# Robot_arm.net
KiCad netlist of a schematic drawn in EAGLE
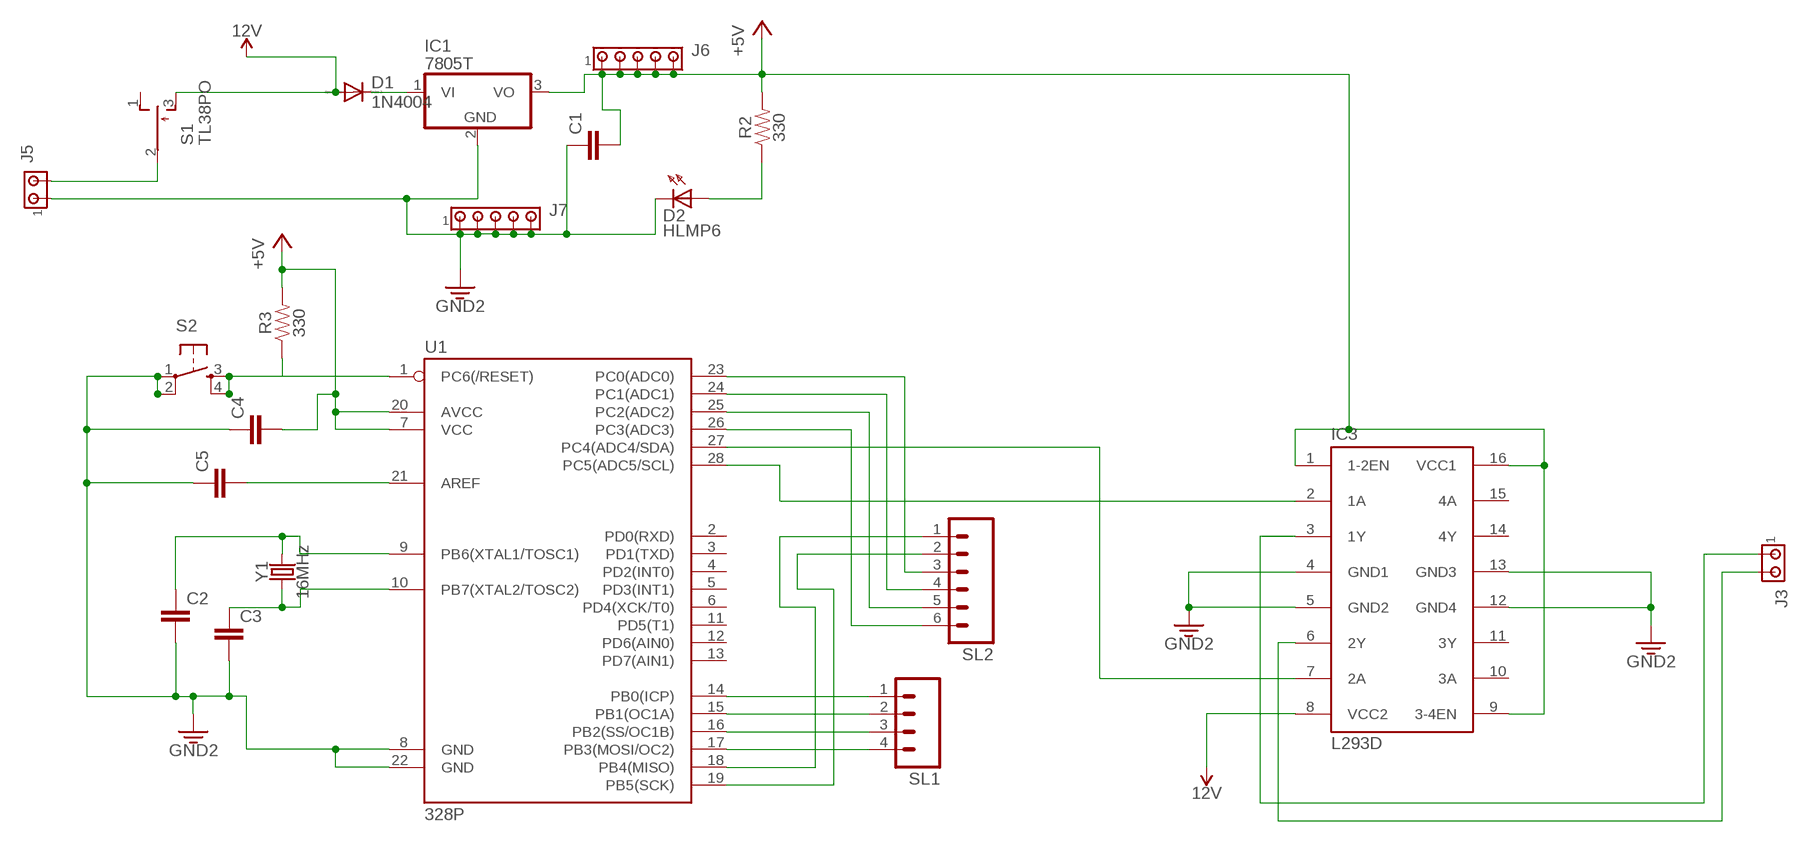
[diagram p0: schematic, sheet 1]

(export (version "E")
  (design (tool "Eeschema 10.0.6"))
  (components
    (comp (ref "C1")
      (value "C5/2.5")
      (footprint "eagle-import:C5B2.5")
      (libsource (lib "eagle-import") (part "C5/2.5"))
    )
    (comp (ref "C2")
      (value "C5/2.5")
      (footprint "eagle-import:C5B2.5")
      (libsource (lib "eagle-import") (part "C5/2.5"))
    )
    (comp (ref "C3")
      (value "C5/2.5")
      (footprint "eagle-import:C5B2.5")
      (libsource (lib "eagle-import") (part "C5/2.5"))
    )
    (comp (ref "C4")
      (value "C5/2.5")
      (footprint "eagle-import:C5B2.5")
      (libsource (lib "eagle-import") (part "C5/2.5"))
    )
    (comp (ref "C5")
      (value "C5/2.5")
      (footprint "eagle-import:C5B2.5")
      (libsource (lib "eagle-import") (part "C5/2.5"))
    )
    (comp (ref "D1")
      (value "1N4004")
      (footprint "eagle-import:DO41-10")
      (libsource (lib "eagle-import") (part "1N4004"))
    )
    (comp (ref "D2")
      (value "HLMP6")
      (footprint "eagle-import:HLMP6")
      (fields (field (name "MF") "AGILENT TECHNOLOGIES") (field (name "MPN") "HLMP-6500"))
      (libsource (lib "eagle-import") (part "HLMP6"))
    )
    (comp (ref "IC1")
      (value "7805T")
      (footprint "eagle-import:TO220H")
      (libsource (lib "eagle-import") (part "78T05"))
    )
    (comp (ref "IC3")
      (value "L293D")
      (footprint "eagle-import:DIL16")
      (libsource (lib "eagle-import") (part "L293D"))
    )
    (comp (ref "J3")
      (value "MTA02-156")
      (footprint "eagle-import:1X2MTA")
      (libsource (lib "eagle-import") (part "MTA02-156"))
    )
    (comp (ref "J5")
      (value "MTA02-156")
      (footprint "eagle-import:1X2MTA")
      (libsource (lib "eagle-import") (part "MTA02-156"))
    )
    (comp (ref "J6")
      (value "MTA05-100")
      (footprint "eagle-import:10X05MTA")
      (libsource (lib "eagle-import") (part "MTA05-100"))
    )
    (comp (ref "J7")
      (value "MTA05-100")
      (footprint "eagle-import:10X05MTA")
      (libsource (lib "eagle-import") (part "MTA05-100"))
    )
    (comp (ref "R2")
      (value "330")
      (footprint "eagle-import:AXIAL-0.3")
      (libsource (lib "eagle-import") (part "330OHM-HORIZ-1/10W-5%"))
    )
    (comp (ref "R3")
      (value "330")
      (footprint "eagle-import:AXIAL-0.3")
      (libsource (lib "eagle-import") (part "330OHM-HORIZ-1/10W-5%"))
    )
    (comp (ref "S1")
      (value "TL38PO")
      (footprint "eagle-import:TL3XPO")
      (libsource (lib "eagle-import") (part "TL38PO"))
    )
    (comp (ref "S2")
      (value "TAC_SWITCHPTH")
      (footprint "eagle-import:TACTILE-PTH")
      (libsource (lib "eagle-import") (part "TAC_SWITCHPTH"))
    )
    (comp (ref "SL1")
      (value "MA04")
      (footprint "eagle-import:04PA")
      (libsource (lib "eagle-import") (part "MA04"))
    )
    (comp (ref "SL2")
      (value "MA06")
      (footprint "eagle-import:06PA")
      (libsource (lib "eagle-import") (part "MA06"))
    )
    (comp (ref "U1")
      (value "328P")
      (footprint "eagle-import:DIP28")
      (libsource (lib "eagle-import") (part "ATMEGA328P_PDIP"))
    )
    (comp (ref "Y1")
      (value "16MHz")
      (footprint "eagle-import:HC49US")
      (libsource (lib "eagle-import") (part "CRYSTAL-16MHZPTH-HC49US"))
    )
  )
  (nets
    (net (code "1") (name "+5V") (class "Default")
      (node (ref "C1") (pin "2") (pinfunction "2_2") (pintype "passive"))
      (node (ref "C4") (pin "2") (pinfunction "2_2") (pintype "passive"))
      (node (ref "IC1") (pin "3") (pinfunction "VO_3") (pintype "passive"))
      (node (ref "IC3") (pin "1") (pinfunction "1-2EN_1") (pintype "input"))
      (node (ref "IC3") (pin "16") (pinfunction "VCC1_16") (pintype "power_in"))
      (node (ref "IC3") (pin "9") (pinfunction "3-4EN_9") (pintype "input"))
      (node (ref "J6") (pin "1") (pinfunction "1_1") (pintype "passive"))
      (node (ref "J6") (pin "2") (pinfunction "2_2") (pintype "passive"))
      (node (ref "J6") (pin "3") (pinfunction "3_3") (pintype "passive"))
      (node (ref "J6") (pin "4") (pinfunction "4_4") (pintype "passive"))
      (node (ref "J6") (pin "5") (pinfunction "5_5") (pintype "passive"))
      (node (ref "R2") (pin "P$2") (pinfunction "2_P$2") (pintype "passive"))
      (node (ref "R3") (pin "P$2") (pinfunction "2_P$2") (pintype "passive"))
      (node (ref "U1") (pin "20") (pinfunction "AVCC_20") (pintype "bidirectional"))
      (node (ref "U1") (pin "7") (pinfunction "VCC_7") (pintype "bidirectional"))
    )
    (net (code "2") (name "12V") (class "Default")
      (node (ref "D1") (pin "A") (pinfunction "A_A") (pintype "passive"))
      (node (ref "IC3") (pin "8") (pinfunction "VCC2_8") (pintype "power_in"))
      (node (ref "S1") (pin "3") (pinfunction "S_3") (pintype "passive"))
    )
    (net (code "3") (name "GND2") (class "Default")
      (node (ref "C1") (pin "1") (pinfunction "1_1") (pintype "passive"))
      (node (ref "C2") (pin "2") (pinfunction "2_2") (pintype "passive"))
      (node (ref "C3") (pin "2") (pinfunction "2_2") (pintype "passive"))
      (node (ref "C4") (pin "1") (pinfunction "1_1") (pintype "passive"))
      (node (ref "C5") (pin "1") (pinfunction "1_1") (pintype "passive"))
      (node (ref "D2") (pin "K") (pinfunction "K_K") (pintype "passive"))
      (node (ref "IC1") (pin "2") (pinfunction "GND_2") (pintype "passive"))
      (node (ref "IC3") (pin "12") (pinfunction "GND4_12") (pintype "power_in"))
      (node (ref "IC3") (pin "13") (pinfunction "GND3_13") (pintype "power_in"))
      (node (ref "IC3") (pin "4") (pinfunction "GND1_4") (pintype "power_in"))
      (node (ref "IC3") (pin "5") (pinfunction "GND2_5") (pintype "power_in"))
      (node (ref "J5") (pin "1") (pinfunction "1_1") (pintype "passive"))
      (node (ref "J7") (pin "1") (pinfunction "1_1") (pintype "passive"))
      (node (ref "J7") (pin "2") (pinfunction "2_2") (pintype "passive"))
      (node (ref "J7") (pin "3") (pinfunction "3_3") (pintype "passive"))
      (node (ref "J7") (pin "4") (pinfunction "4_4") (pintype "passive"))
      (node (ref "J7") (pin "5") (pinfunction "5_5") (pintype "passive"))
      (node (ref "S2") (pin "1") (pinfunction "1_1") (pintype "passive"))
      (node (ref "S2") (pin "2") (pinfunction "2_2") (pintype "passive"))
      (node (ref "U1") (pin "22") (pinfunction "GND_22") (pintype "bidirectional"))
      (node (ref "U1") (pin "8") (pinfunction "GND_8") (pintype "bidirectional"))
    )
    (net (code "4") (name "Net-(IC1-VI)") (class "Default")
      (node (ref "D1") (pin "C") (pinfunction "C_C") (pintype "passive"))
      (node (ref "IC1") (pin "1") (pinfunction "VI_1") (pintype "input"))
    )
    (net (code "5") (name "Net-(IC3-1A)") (class "Default")
      (node (ref "IC3") (pin "2") (pinfunction "1A_2") (pintype "input"))
      (node (ref "U1") (pin "28") (pinfunction "PC5(ADC5/SCL)_28") (pintype "bidirectional"))
    )
    (net (code "6") (name "Net-(IC3-1Y)") (class "Default")
      (node (ref "IC3") (pin "3") (pinfunction "1Y_3") (pintype "output"))
      (node (ref "J3") (pin "1") (pinfunction "1_1") (pintype "passive"))
    )
    (net (code "7") (name "Net-(IC3-2A)") (class "Default")
      (node (ref "IC3") (pin "7") (pinfunction "2A_7") (pintype "input"))
      (node (ref "U1") (pin "27") (pinfunction "PC4(ADC4/SDA)_27") (pintype "bidirectional"))
    )
    (net (code "8") (name "Net-(IC3-2Y)") (class "Default")
      (node (ref "IC3") (pin "6") (pinfunction "2Y_6") (pintype "output"))
      (node (ref "J3") (pin "2") (pinfunction "2_2") (pintype "passive"))
    )
    (net (code "9") (name "Net-(R2-1)") (class "Default")
      (node (ref "D2") (pin "A") (pinfunction "A_A") (pintype "passive"))
      (node (ref "R2") (pin "P$1") (pinfunction "1_P$1") (pintype "passive"))
    )
    (net (code "10") (name "Net-(R3-1)") (class "Default")
      (node (ref "R3") (pin "P$1") (pinfunction "1_P$1") (pintype "passive"))
      (node (ref "S2") (pin "3") (pinfunction "3_3") (pintype "passive"))
      (node (ref "S2") (pin "4") (pinfunction "4_4") (pintype "passive"))
      (node (ref "U1") (pin "1") (pinfunction "PC6(/RESET)_1") (pintype "bidirectional"))
    )
    (net (code "11") (name "Net-(S1-P)") (class "Default")
      (node (ref "J5") (pin "2") (pinfunction "2_2") (pintype "passive"))
      (node (ref "S1") (pin "2") (pinfunction "P_2") (pintype "passive"))
    )
    (net (code "12") (name "Net-(U1-AREF)") (class "Default")
      (node (ref "C5") (pin "2") (pinfunction "2_2") (pintype "passive"))
      (node (ref "U1") (pin "21") (pinfunction "AREF_21") (pintype "bidirectional"))
    )
    (net (code "13") (name "Net-(U1-PB0(ICP))") (class "Default")
      (node (ref "SL1") (pin "1") (pinfunction "1_1") (pintype "passive"))
      (node (ref "U1") (pin "14") (pinfunction "PB0(ICP)_14") (pintype "bidirectional"))
    )
    (net (code "14") (name "Net-(U1-PB1(OC1A))") (class "Default")
      (node (ref "SL1") (pin "2") (pinfunction "2_2") (pintype "passive"))
      (node (ref "U1") (pin "15") (pinfunction "PB1(OC1A)_15") (pintype "bidirectional"))
    )
    (net (code "15") (name "Net-(U1-PB2(SS{slash}OC1B))") (class "Default")
      (node (ref "SL1") (pin "3") (pinfunction "3_3") (pintype "passive"))
      (node (ref "U1") (pin "16") (pinfunction "PB2(SS/OC1B)_16") (pintype "bidirectional"))
    )
    (net (code "16") (name "Net-(U1-PB3(MOSI{slash}OC2))") (class "Default")
      (node (ref "SL1") (pin "4") (pinfunction "4_4") (pintype "passive"))
      (node (ref "U1") (pin "17") (pinfunction "PB3(MOSI/OC2)_17") (pintype "bidirectional"))
    )
    (net (code "17") (name "Net-(U1-PB4(MISO))") (class "Default")
      (node (ref "SL2") (pin "1") (pinfunction "1_1") (pintype "passive"))
      (node (ref "U1") (pin "18") (pinfunction "PB4(MISO)_18") (pintype "bidirectional"))
    )
    (net (code "18") (name "Net-(U1-PB5(SCK))") (class "Default")
      (node (ref "SL2") (pin "2") (pinfunction "2_2") (pintype "passive"))
      (node (ref "U1") (pin "19") (pinfunction "PB5(SCK)_19") (pintype "bidirectional"))
    )
    (net (code "19") (name "Net-(U1-PB6(XTAL1{slash}TOSC1))") (class "Default")
      (node (ref "C2") (pin "1") (pinfunction "1_1") (pintype "passive"))
      (node (ref "U1") (pin "9") (pinfunction "PB6(XTAL1/TOSC1)_9") (pintype "bidirectional"))
      (node (ref "Y1") (pin "2") (pinfunction "2_2") (pintype "passive"))
    )
    (net (code "20") (name "Net-(U1-PB7(XTAL2{slash}TOSC2))") (class "Default")
      (node (ref "C3") (pin "1") (pinfunction "1_1") (pintype "passive"))
      (node (ref "U1") (pin "10") (pinfunction "PB7(XTAL2/TOSC2)_10") (pintype "bidirectional"))
      (node (ref "Y1") (pin "1") (pinfunction "1_1") (pintype "passive"))
    )
    (net (code "21") (name "Net-(U1-PC0(ADC0))") (class "Default")
      (node (ref "SL2") (pin "3") (pinfunction "3_3") (pintype "passive"))
      (node (ref "U1") (pin "23") (pinfunction "PC0(ADC0)_23") (pintype "bidirectional"))
    )
    (net (code "22") (name "Net-(U1-PC1(ADC1))") (class "Default")
      (node (ref "SL2") (pin "4") (pinfunction "4_4") (pintype "passive"))
      (node (ref "U1") (pin "24") (pinfunction "PC1(ADC1)_24") (pintype "bidirectional"))
    )
    (net (code "23") (name "Net-(U1-PC2(ADC2))") (class "Default")
      (node (ref "SL2") (pin "5") (pinfunction "5_5") (pintype "passive"))
      (node (ref "U1") (pin "25") (pinfunction "PC2(ADC2)_25") (pintype "bidirectional"))
    )
    (net (code "24") (name "Net-(U1-PC3(ADC3))") (class "Default")
      (node (ref "SL2") (pin "6") (pinfunction "6_6") (pintype "passive"))
      (node (ref "U1") (pin "26") (pinfunction "PC3(ADC3)_26") (pintype "bidirectional"))
    )
    (net (code "25") (name "unconnected-(IC3-3A-Pad10)") (class "Default")
      (node (ref "IC3") (pin "10") (pinfunction "3A_10") (pintype "input"))
    )
    (net (code "26") (name "unconnected-(IC3-3Y-Pad11)") (class "Default")
      (node (ref "IC3") (pin "11") (pinfunction "3Y_11") (pintype "output"))
    )
    (net (code "27") (name "unconnected-(IC3-4A-Pad15)") (class "Default")
      (node (ref "IC3") (pin "15") (pinfunction "4A_15") (pintype "input"))
    )
    (net (code "28") (name "unconnected-(IC3-4Y-Pad14)") (class "Default")
      (node (ref "IC3") (pin "14") (pinfunction "4Y_14") (pintype "output"))
    )
    (net (code "29") (name "unconnected-(S1-O-Pad1)") (class "Default")
      (node (ref "S1") (pin "1") (pinfunction "O_1") (pintype "passive"))
    )
    (net (code "30") (name "unconnected-(U1-PD0(RXD)-Pad2)") (class "Default")
      (node (ref "U1") (pin "2") (pinfunction "PD0(RXD)_2") (pintype "bidirectional"))
    )
    (net (code "31") (name "unconnected-(U1-PD1(TXD)-Pad3)") (class "Default")
      (node (ref "U1") (pin "3") (pinfunction "PD1(TXD)_3") (pintype "bidirectional"))
    )
    (net (code "32") (name "unconnected-(U1-PD2(INT0)-Pad4)") (class "Default")
      (node (ref "U1") (pin "4") (pinfunction "PD2(INT0)_4") (pintype "bidirectional"))
    )
    (net (code "33") (name "unconnected-(U1-PD3(INT1)-Pad5)") (class "Default")
      (node (ref "U1") (pin "5") (pinfunction "PD3(INT1)_5") (pintype "bidirectional"))
    )
    (net (code "34") (name "unconnected-(U1-PD4(XCK{slash}T0)-Pad6)") (class "Default")
      (node (ref "U1") (pin "6") (pinfunction "PD4(XCK/T0)_6") (pintype "bidirectional"))
    )
    (net (code "35") (name "unconnected-(U1-PD5(T1)-Pad11)") (class "Default")
      (node (ref "U1") (pin "11") (pinfunction "PD5(T1)_11") (pintype "bidirectional"))
    )
    (net (code "36") (name "unconnected-(U1-PD6(AIN0)-Pad12)") (class "Default")
      (node (ref "U1") (pin "12") (pinfunction "PD6(AIN0)_12") (pintype "bidirectional"))
    )
    (net (code "37") (name "unconnected-(U1-PD7(AIN1)-Pad13)") (class "Default")
      (node (ref "U1") (pin "13") (pinfunction "PD7(AIN1)_13") (pintype "bidirectional"))
    )
  )
)
